# Sonar-Amplifier-Prototype.net
KiCad netlist of a schematic drawn in EAGLE
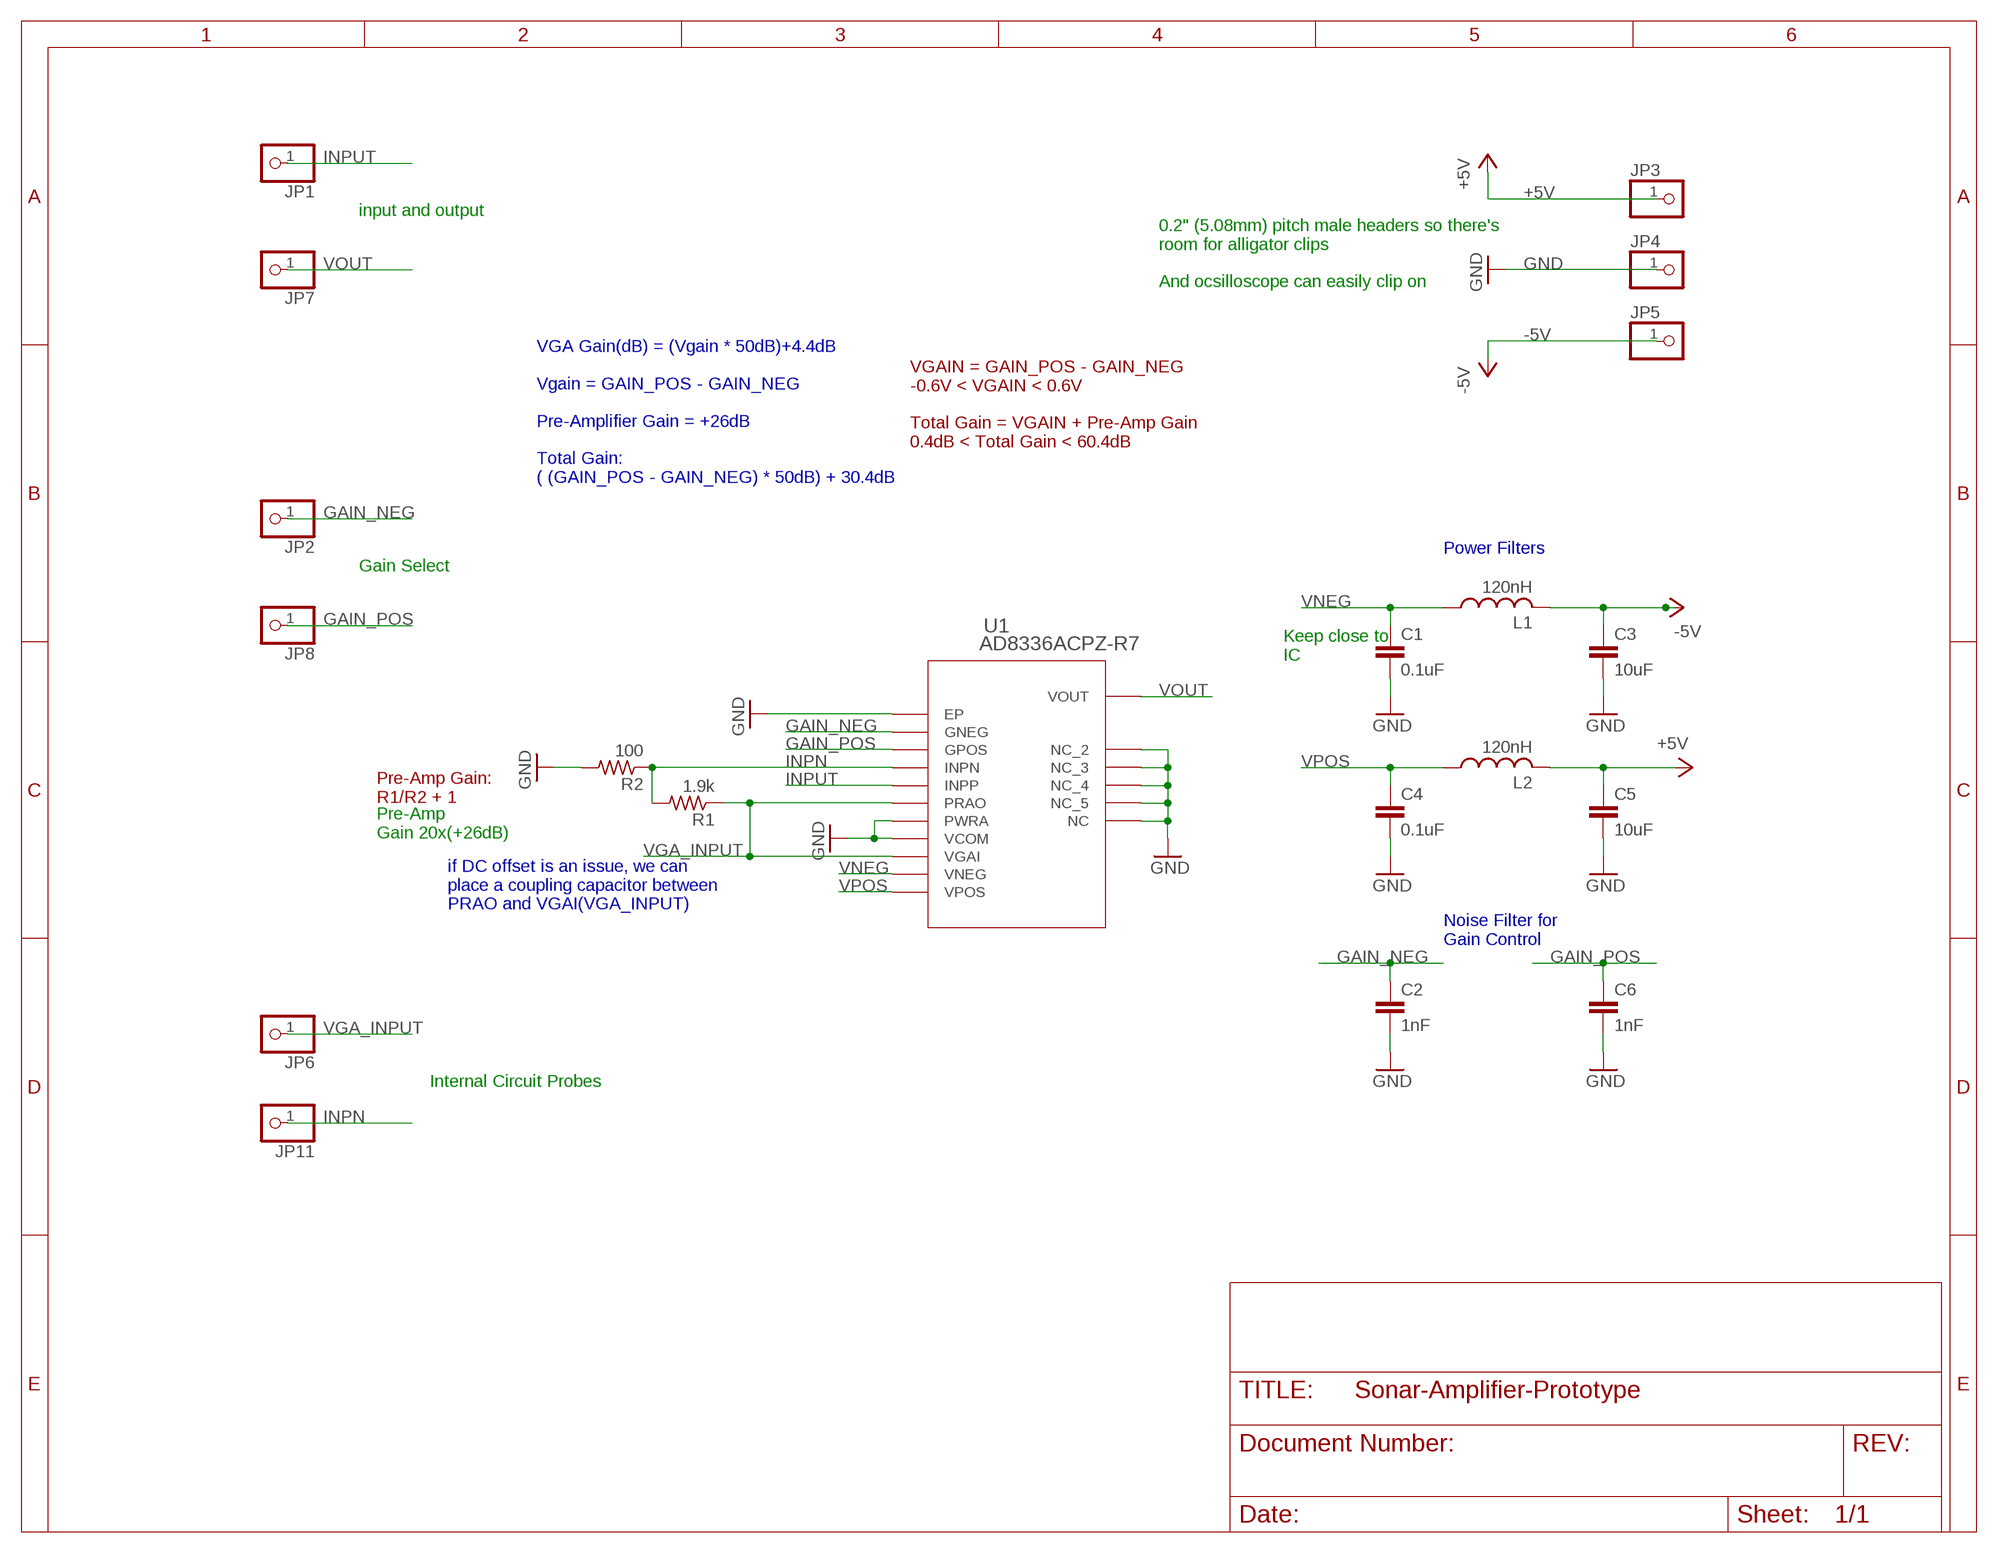
[diagram p0: schematic, sheet 1]

(export (version "E")
  (design (tool "Eeschema 10.0.6"))
  (components
    (comp (ref "C1")
      (value "0.1uF")
      (footprint "eagle-import:C0603")
      (libsource (lib "eagle-import") (part "C-EUC0603"))
    )
    (comp (ref "C2")
      (value "1nF")
      (footprint "eagle-import:C0603")
      (libsource (lib "eagle-import") (part "C-EUC0603"))
    )
    (comp (ref "C3")
      (value "10uF")
      (footprint "eagle-import:C1206")
      (libsource (lib "eagle-import") (part "resistor_348_C-EUC1206"))
    )
    (comp (ref "C4")
      (value "0.1uF")
      (footprint "eagle-import:C0603")
      (libsource (lib "eagle-import") (part "C-EUC0603"))
    )
    (comp (ref "C5")
      (value "10uF")
      (footprint "eagle-import:C1206")
      (libsource (lib "eagle-import") (part "resistor_348_C-EUC1206"))
    )
    (comp (ref "C6")
      (value "1nF")
      (footprint "eagle-import:C0603")
      (libsource (lib "eagle-import") (part "C-EUC0603"))
    )
    (comp (ref "JP1")
      (value "PINHD-1X1")
      (footprint "eagle-import:1X01")
      (libsource (lib "eagle-import") (part "PINHD-1X1"))
    )
    (comp (ref "JP2")
      (value "PINHD-1X1")
      (footprint "eagle-import:1X01")
      (libsource (lib "eagle-import") (part "PINHD-1X1"))
    )
    (comp (ref "JP3")
      (value "PINHD-1X1")
      (footprint "eagle-import:1X01")
      (libsource (lib "eagle-import") (part "PINHD-1X1"))
    )
    (comp (ref "JP4")
      (value "PINHD-1X1")
      (footprint "eagle-import:1X01")
      (libsource (lib "eagle-import") (part "PINHD-1X1"))
    )
    (comp (ref "JP5")
      (value "PINHD-1X1")
      (footprint "eagle-import:1X01")
      (libsource (lib "eagle-import") (part "PINHD-1X1"))
    )
    (comp (ref "JP6")
      (value "PINHD-1X1")
      (footprint "eagle-import:1X01")
      (libsource (lib "eagle-import") (part "PINHD-1X1"))
    )
    (comp (ref "JP7")
      (value "PINHD-1X1")
      (footprint "eagle-import:1X01")
      (libsource (lib "eagle-import") (part "PINHD-1X1"))
    )
    (comp (ref "JP8")
      (value "PINHD-1X1")
      (footprint "eagle-import:1X01")
      (libsource (lib "eagle-import") (part "PINHD-1X1"))
    )
    (comp (ref "JP11")
      (value "PINHD-1X1")
      (footprint "eagle-import:1X01")
      (libsource (lib "eagle-import") (part "PINHD-1X1"))
    )
    (comp (ref "L1")
      (value "120nH")
      (footprint "eagle-import:L3225P")
      (libsource (lib "eagle-import") (part "L-USL3225P"))
    )
    (comp (ref "L2")
      (value "120nH")
      (footprint "eagle-import:L3225P")
      (libsource (lib "eagle-import") (part "L-USL3225P"))
    )
    (comp (ref "R1")
      (value "1.9k")
      (footprint "eagle-import:R0603")
      (libsource (lib "eagle-import") (part "R-US_R0603"))
    )
    (comp (ref "R2")
      (value "100")
      (footprint "eagle-import:R0603")
      (libsource (lib "eagle-import") (part "R-US_R0603"))
    )
    (comp (ref "U1")
      (value "AD8336ACPZ-R7")
      (footprint "eagle-import:CP_16_4")
      (fields (field (name "MANUFACTURER_PART_NUMBER") "AD8336ACPZR7"))
      (libsource (lib "eagle-import") (part "AD8336ACPZ-R7"))
    )
  )
  (nets
    (net (code "1") (name "+5V") (class "Default")
      (node (ref "C5") (pin "1") (pinfunction "1_1") (pintype "passive"))
      (node (ref "JP3") (pin "1") (pinfunction "1_1") (pintype "passive"))
      (node (ref "L2") (pin "2") (pinfunction "2_2") (pintype "passive"))
    )
    (net (code "2") (name "-5V") (class "Default")
      (node (ref "C3") (pin "1") (pinfunction "1_1") (pintype "passive"))
      (node (ref "JP5") (pin "1") (pinfunction "1_1") (pintype "passive"))
      (node (ref "L1") (pin "2") (pinfunction "2_2") (pintype "passive"))
    )
    (net (code "3") (name "/GAIN_NEG") (class "Default")
      (node (ref "C2") (pin "1") (pinfunction "1_1") (pintype "passive"))
      (node (ref "JP2") (pin "1") (pinfunction "1_1") (pintype "passive"))
      (node (ref "U1") (pin "GNEG") (pinfunction "GNEG_GNEG") (pintype "passive"))
    )
    (net (code "4") (name "/GAIN_POS") (class "Default")
      (node (ref "C6") (pin "1") (pinfunction "1_1") (pintype "passive"))
      (node (ref "JP8") (pin "1") (pinfunction "1_1") (pintype "passive"))
      (node (ref "U1") (pin "GPOS") (pinfunction "GPOS_GPOS") (pintype "passive"))
    )
    (net (code "5") (name "/INPN") (class "Default")
      (node (ref "JP11") (pin "1") (pinfunction "1_1") (pintype "passive"))
      (node (ref "R1") (pin "2") (pinfunction "2_2") (pintype "passive"))
      (node (ref "R2") (pin "1") (pinfunction "1_1") (pintype "passive"))
      (node (ref "U1") (pin "INPN") (pinfunction "INPN_INPN") (pintype "passive"))
    )
    (net (code "6") (name "/INPUT") (class "Default")
      (node (ref "JP1") (pin "1") (pinfunction "1_1") (pintype "passive"))
      (node (ref "U1") (pin "INPP") (pinfunction "INPP_INPP") (pintype "passive"))
    )
    (net (code "7") (name "/VGA_INPUT") (class "Default")
      (node (ref "JP6") (pin "1") (pinfunction "1_1") (pintype "passive"))
      (node (ref "R1") (pin "1") (pinfunction "1_1") (pintype "passive"))
      (node (ref "U1") (pin "PRAO") (pinfunction "PRAO_PRAO") (pintype "passive"))
      (node (ref "U1") (pin "VGAI") (pinfunction "VGAI_VGAI") (pintype "passive"))
    )
    (net (code "8") (name "/VNEG") (class "Default")
      (node (ref "C1") (pin "1") (pinfunction "1_1") (pintype "passive"))
      (node (ref "L1") (pin "1") (pinfunction "1_1") (pintype "passive"))
      (node (ref "U1") (pin "VNEG") (pinfunction "VNEG_VNEG") (pintype "passive"))
    )
    (net (code "9") (name "/VOUT") (class "Default")
      (node (ref "JP7") (pin "1") (pinfunction "1_1") (pintype "passive"))
      (node (ref "U1") (pin "VOUT") (pinfunction "VOUT_VOUT") (pintype "passive"))
    )
    (net (code "10") (name "/VPOS") (class "Default")
      (node (ref "C4") (pin "1") (pinfunction "1_1") (pintype "passive"))
      (node (ref "L2") (pin "1") (pinfunction "1_1") (pintype "passive"))
      (node (ref "U1") (pin "VPOS") (pinfunction "VPOS_VPOS") (pintype "passive"))
    )
    (net (code "11") (name "GND") (class "Default")
      (node (ref "C1") (pin "2") (pinfunction "2_2") (pintype "passive"))
      (node (ref "C2") (pin "2") (pinfunction "2_2") (pintype "passive"))
      (node (ref "C3") (pin "2") (pinfunction "2_2") (pintype "passive"))
      (node (ref "C4") (pin "2") (pinfunction "2_2") (pintype "passive"))
      (node (ref "C5") (pin "2") (pinfunction "2_2") (pintype "passive"))
      (node (ref "C6") (pin "2") (pinfunction "2_2") (pintype "passive"))
      (node (ref "JP4") (pin "1") (pinfunction "1_1") (pintype "passive"))
      (node (ref "R2") (pin "2") (pinfunction "2_2") (pintype "passive"))
      (node (ref "U1") (pin "GND1") (pinfunction "EP_GND1") (pintype "passive"))
      (node (ref "U1") (pin "NC") (pinfunction "NC_NC") (pintype "passive"))
      (node (ref "U1") (pin "NC1") (pinfunction "NC_2_NC1") (pintype "passive"))
      (node (ref "U1") (pin "NC2") (pinfunction "NC_3_NC2") (pintype "passive"))
      (node (ref "U1") (pin "NC3") (pinfunction "NC_4_NC3") (pintype "passive"))
      (node (ref "U1") (pin "NC4") (pinfunction "NC_5_NC4") (pintype "passive"))
      (node (ref "U1") (pin "PWRA") (pinfunction "PWRA_PWRA") (pintype "passive"))
      (node (ref "U1") (pin "VCOM") (pinfunction "VCOM_VCOM") (pintype "passive"))
    )
  )
)
